# FitzSPA.net
KiCad netlist of a schematic drawn in EAGLE
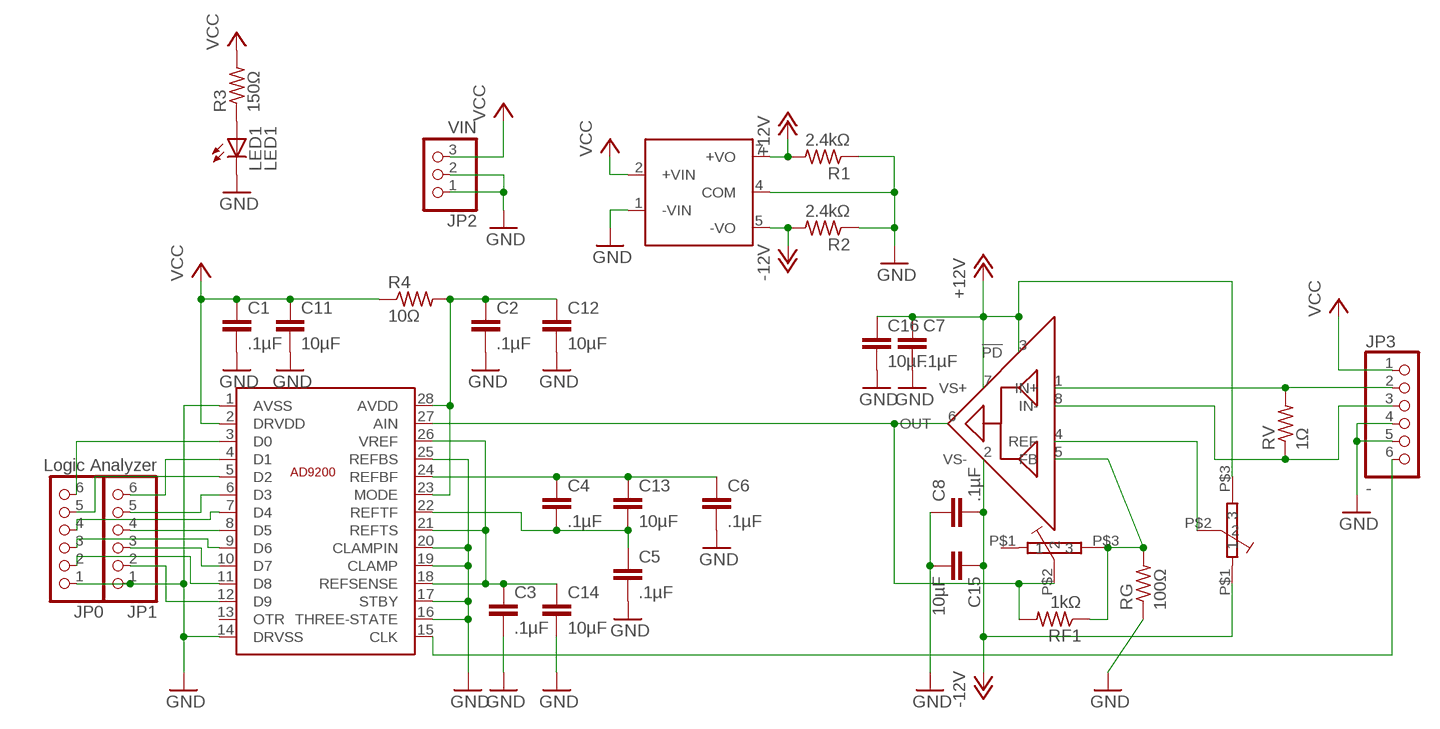
[diagram p0: schematic, sheet 1]

(export (version "E")
  (design (tool "Eeschema 10.0.6"))
  (components
    (comp (ref "C1")
      (value ".1µF")
      (footprint "eagle-import:C0603")
      (libsource (lib "eagle-import") (part "C-EUC0603"))
    )
    (comp (ref "C2")
      (value ".1µF")
      (footprint "eagle-import:C0603")
      (libsource (lib "eagle-import") (part "C-EUC0603"))
    )
    (comp (ref "C3")
      (value ".1µF")
      (footprint "eagle-import:C0603")
      (libsource (lib "eagle-import") (part "C-EUC0603"))
    )
    (comp (ref "C4")
      (value ".1µF")
      (footprint "eagle-import:C0603")
      (libsource (lib "eagle-import") (part "C-EUC0603"))
    )
    (comp (ref "C5")
      (value ".1µF")
      (footprint "eagle-import:C0603")
      (libsource (lib "eagle-import") (part "C-EUC0603"))
    )
    (comp (ref "C6")
      (value ".1µF")
      (footprint "eagle-import:C0603")
      (libsource (lib "eagle-import") (part "C-EUC0603"))
    )
    (comp (ref "C7")
      (value ".1µF")
      (footprint "eagle-import:C0603")
      (libsource (lib "eagle-import") (part "C-EUC0603"))
    )
    (comp (ref "C8")
      (value ".1µF")
      (footprint "eagle-import:C0603")
      (libsource (lib "eagle-import") (part "C-EUC0603"))
    )
    (comp (ref "C11")
      (value "10µF")
      (footprint "eagle-import:C0805")
      (libsource (lib "eagle-import") (part "C-EUC0805"))
    )
    (comp (ref "C12")
      (value "10µF")
      (footprint "eagle-import:C0805")
      (libsource (lib "eagle-import") (part "C-EUC0805"))
    )
    (comp (ref "C13")
      (value "10µF")
      (footprint "eagle-import:C0805")
      (libsource (lib "eagle-import") (part "C-EUC0805"))
    )
    (comp (ref "C14")
      (value "10µF")
      (footprint "eagle-import:C0805")
      (libsource (lib "eagle-import") (part "C-EUC0805"))
    )
    (comp (ref "C15")
      (value "10µF")
      (footprint "eagle-import:C0805")
      (libsource (lib "eagle-import") (part "C-EUC0805"))
    )
    (comp (ref "C16")
      (value "10µF")
      (footprint "eagle-import:C0805")
      (libsource (lib "eagle-import") (part "C-EUC0805"))
    )
    (comp (ref "JP0")
      (value "PINHD-1X6LOCK")
      (footprint "eagle-import:1X06-BIGLOCK")
      (libsource (lib "eagle-import") (part "PINHD-1X6LOCK"))
    )
    (comp (ref "JP1")
      (value "Logic Analyzer")
      (footprint "eagle-import:1X06-BIGLOCK")
      (libsource (lib "eagle-import") (part "PINHD-1X6LOCK"))
    )
    (comp (ref "JP2")
      (value "VIN")
      (footprint "eagle-import:1X03")
      (libsource (lib "eagle-import") (part "PINHD-1X3"))
    )
    (comp (ref "JP3")
      (value "-")
      (footprint "eagle-import:1X06-BIGLOCK")
      (libsource (lib "eagle-import") (part "PINHD-1X6LOCK"))
    )
    (comp (ref "LED1")
      (value "LED1")
      (footprint "eagle-import:CHIPLED_0603")
      (libsource (lib "eagle-import") (part "LEDCHIPLED_0603"))
    )
    (comp (ref "R1")
      (value "2.4kΩ")
      (footprint "eagle-import:R0603")
      (libsource (lib "eagle-import") (part "R-US_R0603"))
    )
    (comp (ref "R2")
      (value "2.4kΩ")
      (footprint "eagle-import:R0603")
      (libsource (lib "eagle-import") (part "R-US_R0603"))
    )
    (comp (ref "R3")
      (value "150Ω")
      (footprint "eagle-import:R0603")
      (libsource (lib "eagle-import") (part "R-US_R0603"))
    )
    (comp (ref "R4")
      (value "10Ω")
      (footprint "eagle-import:R0603")
      (libsource (lib "eagle-import") (part "R-US_R0603"))
    )
    (comp (ref "RF")
      (value "10kΩ")
      (footprint "eagle-import:MODEL84POT")
      (libsource (lib "eagle-import") (part "MODEL84POT"))
    )
    (comp (ref "RF1")
      (value "1kΩ")
      (footprint "eagle-import:R0603")
      (libsource (lib "eagle-import") (part "R-US_R0603"))
    )
    (comp (ref "RF2")
      (value "10kΩ")
      (footprint "eagle-import:MODEL84POT")
      (libsource (lib "eagle-import") (part "MODEL84POT"))
    )
    (comp (ref "RG")
      (value "100Ω")
      (footprint "eagle-import:R0603")
      (libsource (lib "eagle-import") (part "R-US_R0603"))
    )
    (comp (ref "RV")
      (value "1Ω")
      (footprint "eagle-import:R0603")
      (libsource (lib "eagle-import") (part "R-US_R0603"))
    )
    (comp (ref "U1")
      (value "AD9200ARZ")
      (footprint "eagle-import:SSOP28")
      (libsource (lib "eagle-import") (part "AD9200ARZ"))
    )
    (comp (ref "U2")
      (value "AD8129ARMZ")
      (footprint "eagle-import:MSOP8")
      (libsource (lib "eagle-import") (part "AD8129ARMZ"))
    )
    (comp (ref "U3")
      (value "VAT1-SMT")
      (footprint "eagle-import:VAT1-SMT")
      (libsource (lib "eagle-import") (part "VAT1-SMT"))
    )
  )
  (nets
    (net (code "1") (name "+12V") (class "Default")
      (node (ref "C16") (pin "1") (pinfunction "1_1") (pintype "passive"))
      (node (ref "C7") (pin "1") (pinfunction "1_1") (pintype "passive"))
      (node (ref "R1") (pin "2") (pinfunction "2_2") (pintype "passive"))
      (node (ref "RF2") (pin "P$3") (pinfunction "3_P$3") (pintype "bidirectional"))
      (node (ref "U2") (pin "3") (pinfunction "~{PD}_3") (pintype "bidirectional"))
      (node (ref "U2") (pin "7") (pinfunction "VS+_7") (pintype "bidirectional"))
      (node (ref "U3") (pin "7") (pinfunction "+VO_7") (pintype "bidirectional"))
    )
    (net (code "2") (name "-12V") (class "Default")
      (node (ref "C15") (pin "1") (pinfunction "1_1") (pintype "passive"))
      (node (ref "C8") (pin "2") (pinfunction "2_2") (pintype "passive"))
      (node (ref "R2") (pin "2") (pinfunction "2_2") (pintype "passive"))
      (node (ref "RF2") (pin "P$1") (pinfunction "1_P$1") (pintype "bidirectional"))
      (node (ref "U2") (pin "2") (pinfunction "VS-_2") (pintype "bidirectional"))
      (node (ref "U3") (pin "5") (pinfunction "-VO_5") (pintype "bidirectional"))
    )
    (net (code "3") (name "GND") (class "Default")
      (node (ref "C1") (pin "2") (pinfunction "2_2") (pintype "passive"))
      (node (ref "C11") (pin "2") (pinfunction "2_2") (pintype "passive"))
      (node (ref "C12") (pin "2") (pinfunction "2_2") (pintype "passive"))
      (node (ref "C14") (pin "2") (pinfunction "2_2") (pintype "passive"))
      (node (ref "C15") (pin "2") (pinfunction "2_2") (pintype "passive"))
      (node (ref "C16") (pin "2") (pinfunction "2_2") (pintype "passive"))
      (node (ref "C2") (pin "2") (pinfunction "2_2") (pintype "passive"))
      (node (ref "C3") (pin "2") (pinfunction "2_2") (pintype "passive"))
      (node (ref "C5") (pin "2") (pinfunction "2_2") (pintype "passive"))
      (node (ref "C6") (pin "2") (pinfunction "2_2") (pintype "passive"))
      (node (ref "C7") (pin "2") (pinfunction "2_2") (pintype "passive"))
      (node (ref "C8") (pin "1") (pinfunction "1_1") (pintype "passive"))
      (node (ref "JP0") (pin "1") (pinfunction "1_1") (pintype "passive"))
      (node (ref "JP1") (pin "1") (pinfunction "1_1") (pintype "passive"))
      (node (ref "JP2") (pin "1") (pinfunction "1_1") (pintype "passive"))
      (node (ref "JP2") (pin "2") (pinfunction "2_2") (pintype "passive"))
      (node (ref "JP3") (pin "4") (pinfunction "4_4") (pintype "passive"))
      (node (ref "JP3") (pin "5") (pinfunction "5_5") (pintype "passive"))
      (node (ref "LED1") (pin "C") (pinfunction "C_C") (pintype "passive"))
      (node (ref "R1") (pin "1") (pinfunction "1_1") (pintype "passive"))
      (node (ref "R2") (pin "1") (pinfunction "1_1") (pintype "passive"))
      (node (ref "RG") (pin "1") (pinfunction "1_1") (pintype "passive"))
      (node (ref "U1") (pin "1") (pinfunction "AVSS_1") (pintype "bidirectional"))
      (node (ref "U1") (pin "14") (pinfunction "DRVSS_14") (pintype "bidirectional"))
      (node (ref "U1") (pin "16") (pinfunction "THREE-STATE_16") (pintype "bidirectional"))
      (node (ref "U1") (pin "17") (pinfunction "STBY_17") (pintype "bidirectional"))
      (node (ref "U1") (pin "19") (pinfunction "CLAMP_19") (pintype "bidirectional"))
      (node (ref "U1") (pin "20") (pinfunction "CLAMPIN_20") (pintype "bidirectional"))
      (node (ref "U1") (pin "25") (pinfunction "REFBS_25") (pintype "bidirectional"))
      (node (ref "U3") (pin "1") (pinfunction "-VIN_1") (pintype "bidirectional"))
      (node (ref "U3") (pin "4") (pinfunction "COM_4") (pintype "bidirectional"))
    )
    (net (code "4") (name "Net-(LED1-PadA)") (class "Default")
      (node (ref "LED1") (pin "A") (pinfunction "A_A") (pintype "passive"))
      (node (ref "R3") (pin "1") (pinfunction "1_1") (pintype "passive"))
    )
    (net (code "5") (name "Net-(RF-2)") (class "Default")
      (node (ref "RF") (pin "P$2") (pinfunction "2_P$2") (pintype "bidirectional"))
      (node (ref "RF1") (pin "2") (pinfunction "2_2") (pintype "passive"))
      (node (ref "U1") (pin "27") (pinfunction "AIN_27") (pintype "bidirectional"))
      (node (ref "U2") (pin "6") (pinfunction "OUT_6") (pintype "bidirectional"))
    )
    (net (code "6") (name "Net-(RF-3)") (class "Default")
      (node (ref "RF") (pin "P$3") (pinfunction "3_P$3") (pintype "bidirectional"))
      (node (ref "RF1") (pin "1") (pinfunction "1_1") (pintype "passive"))
      (node (ref "RG") (pin "2") (pinfunction "2_2") (pintype "passive"))
      (node (ref "U2") (pin "5") (pinfunction "FB_5") (pintype "bidirectional"))
    )
    (net (code "7") (name "Net-(RF2-2)") (class "Default")
      (node (ref "RF2") (pin "P$2") (pinfunction "2_P$2") (pintype "bidirectional"))
      (node (ref "U2") (pin "4") (pinfunction "REF_4") (pintype "bidirectional"))
    )
    (net (code "8") (name "Net-(U1-AVDD)") (class "Default")
      (node (ref "C12") (pin "1") (pinfunction "1_1") (pintype "passive"))
      (node (ref "C2") (pin "1") (pinfunction "1_1") (pintype "passive"))
      (node (ref "R4") (pin "2") (pinfunction "2_2") (pintype "passive"))
      (node (ref "U1") (pin "23") (pinfunction "MODE_23") (pintype "bidirectional"))
      (node (ref "U1") (pin "28") (pinfunction "AVDD_28") (pintype "bidirectional"))
    )
    (net (code "9") (name "Net-(U1-CLK)") (class "Default")
      (node (ref "JP3") (pin "6") (pinfunction "6_6") (pintype "passive"))
      (node (ref "U1") (pin "15") (pinfunction "CLK_15") (pintype "bidirectional"))
    )
    (net (code "10") (name "Net-(U1-D0)") (class "Default")
      (node (ref "JP0") (pin "6") (pinfunction "6_6") (pintype "passive"))
      (node (ref "U1") (pin "3") (pinfunction "D0_3") (pintype "bidirectional"))
    )
    (net (code "11") (name "Net-(U1-D1)") (class "Default")
      (node (ref "JP1") (pin "6") (pinfunction "6_6") (pintype "passive"))
      (node (ref "U1") (pin "4") (pinfunction "D1_4") (pintype "bidirectional"))
    )
    (net (code "12") (name "Net-(U1-D2)") (class "Default")
      (node (ref "JP0") (pin "5") (pinfunction "5_5") (pintype "passive"))
      (node (ref "U1") (pin "5") (pinfunction "D2_5") (pintype "bidirectional"))
    )
    (net (code "13") (name "Net-(U1-D3)") (class "Default")
      (node (ref "JP1") (pin "5") (pinfunction "5_5") (pintype "passive"))
      (node (ref "U1") (pin "6") (pinfunction "D3_6") (pintype "bidirectional"))
    )
    (net (code "14") (name "Net-(U1-D4)") (class "Default")
      (node (ref "JP0") (pin "4") (pinfunction "4_4") (pintype "passive"))
      (node (ref "U1") (pin "7") (pinfunction "D4_7") (pintype "bidirectional"))
    )
    (net (code "15") (name "Net-(U1-D5)") (class "Default")
      (node (ref "JP1") (pin "4") (pinfunction "4_4") (pintype "passive"))
      (node (ref "U1") (pin "8") (pinfunction "D5_8") (pintype "bidirectional"))
    )
    (net (code "16") (name "Net-(U1-D6)") (class "Default")
      (node (ref "JP0") (pin "3") (pinfunction "3_3") (pintype "passive"))
      (node (ref "U1") (pin "9") (pinfunction "D6_9") (pintype "bidirectional"))
    )
    (net (code "17") (name "Net-(U1-D7)") (class "Default")
      (node (ref "JP1") (pin "3") (pinfunction "3_3") (pintype "passive"))
      (node (ref "U1") (pin "10") (pinfunction "D7_10") (pintype "bidirectional"))
    )
    (net (code "18") (name "Net-(U1-D8)") (class "Default")
      (node (ref "JP0") (pin "2") (pinfunction "2_2") (pintype "passive"))
      (node (ref "U1") (pin "11") (pinfunction "D8_11") (pintype "bidirectional"))
    )
    (net (code "19") (name "Net-(U1-D9)") (class "Default")
      (node (ref "JP1") (pin "2") (pinfunction "2_2") (pintype "passive"))
      (node (ref "U1") (pin "12") (pinfunction "D9_12") (pintype "bidirectional"))
    )
    (net (code "20") (name "Net-(U1-REFBF)") (class "Default")
      (node (ref "C13") (pin "1") (pinfunction "1_1") (pintype "passive"))
      (node (ref "C4") (pin "1") (pinfunction "1_1") (pintype "passive"))
      (node (ref "C6") (pin "1") (pinfunction "1_1") (pintype "passive"))
      (node (ref "U1") (pin "24") (pinfunction "REFBF_24") (pintype "bidirectional"))
    )
    (net (code "21") (name "Net-(U1-REFSENSE)") (class "Default")
      (node (ref "C14") (pin "1") (pinfunction "1_1") (pintype "passive"))
      (node (ref "C3") (pin "1") (pinfunction "1_1") (pintype "passive"))
      (node (ref "U1") (pin "18") (pinfunction "REFSENSE_18") (pintype "bidirectional"))
      (node (ref "U1") (pin "21") (pinfunction "REFTS_21") (pintype "bidirectional"))
      (node (ref "U1") (pin "26") (pinfunction "VREF_26") (pintype "bidirectional"))
    )
    (net (code "22") (name "Net-(U1-REFTF)") (class "Default")
      (node (ref "C13") (pin "2") (pinfunction "2_2") (pintype "passive"))
      (node (ref "C4") (pin "2") (pinfunction "2_2") (pintype "passive"))
      (node (ref "C5") (pin "1") (pinfunction "1_1") (pintype "passive"))
      (node (ref "U1") (pin "22") (pinfunction "REFTF_22") (pintype "bidirectional"))
    )
    (net (code "23") (name "Net-(U2-IN+)") (class "Default")
      (node (ref "JP3") (pin "2") (pinfunction "2_2") (pintype "passive"))
      (node (ref "RV") (pin "2") (pinfunction "2_2") (pintype "passive"))
      (node (ref "U2") (pin "1") (pinfunction "IN+_1") (pintype "bidirectional"))
    )
    (net (code "24") (name "Net-(U2-IN-)") (class "Default")
      (node (ref "JP3") (pin "3") (pinfunction "3_3") (pintype "passive"))
      (node (ref "RV") (pin "1") (pinfunction "1_1") (pintype "passive"))
      (node (ref "U2") (pin "8") (pinfunction "IN-_8") (pintype "bidirectional"))
    )
    (net (code "25") (name "VCC") (class "Default")
      (node (ref "C1") (pin "1") (pinfunction "1_1") (pintype "passive"))
      (node (ref "C11") (pin "1") (pinfunction "1_1") (pintype "passive"))
      (node (ref "JP2") (pin "3") (pinfunction "3_3") (pintype "passive"))
      (node (ref "JP3") (pin "1") (pinfunction "1_1") (pintype "passive"))
      (node (ref "R3") (pin "2") (pinfunction "2_2") (pintype "passive"))
      (node (ref "R4") (pin "1") (pinfunction "1_1") (pintype "passive"))
      (node (ref "U1") (pin "2") (pinfunction "DRVDD_2") (pintype "bidirectional"))
      (node (ref "U3") (pin "2") (pinfunction "+VIN_2") (pintype "bidirectional"))
    )
    (net (code "26") (name "unconnected-(RF-1-PadP$1)") (class "Default")
      (node (ref "RF") (pin "P$1") (pinfunction "1_P$1") (pintype "bidirectional"))
    )
    (net (code "27") (name "unconnected-(U1-OTR-Pad13)") (class "Default")
      (node (ref "U1") (pin "13") (pinfunction "OTR_13") (pintype "bidirectional"))
    )
  )
)
